# magloop_ad8129.net
KiCad netlist of a schematic drawn in EAGLE
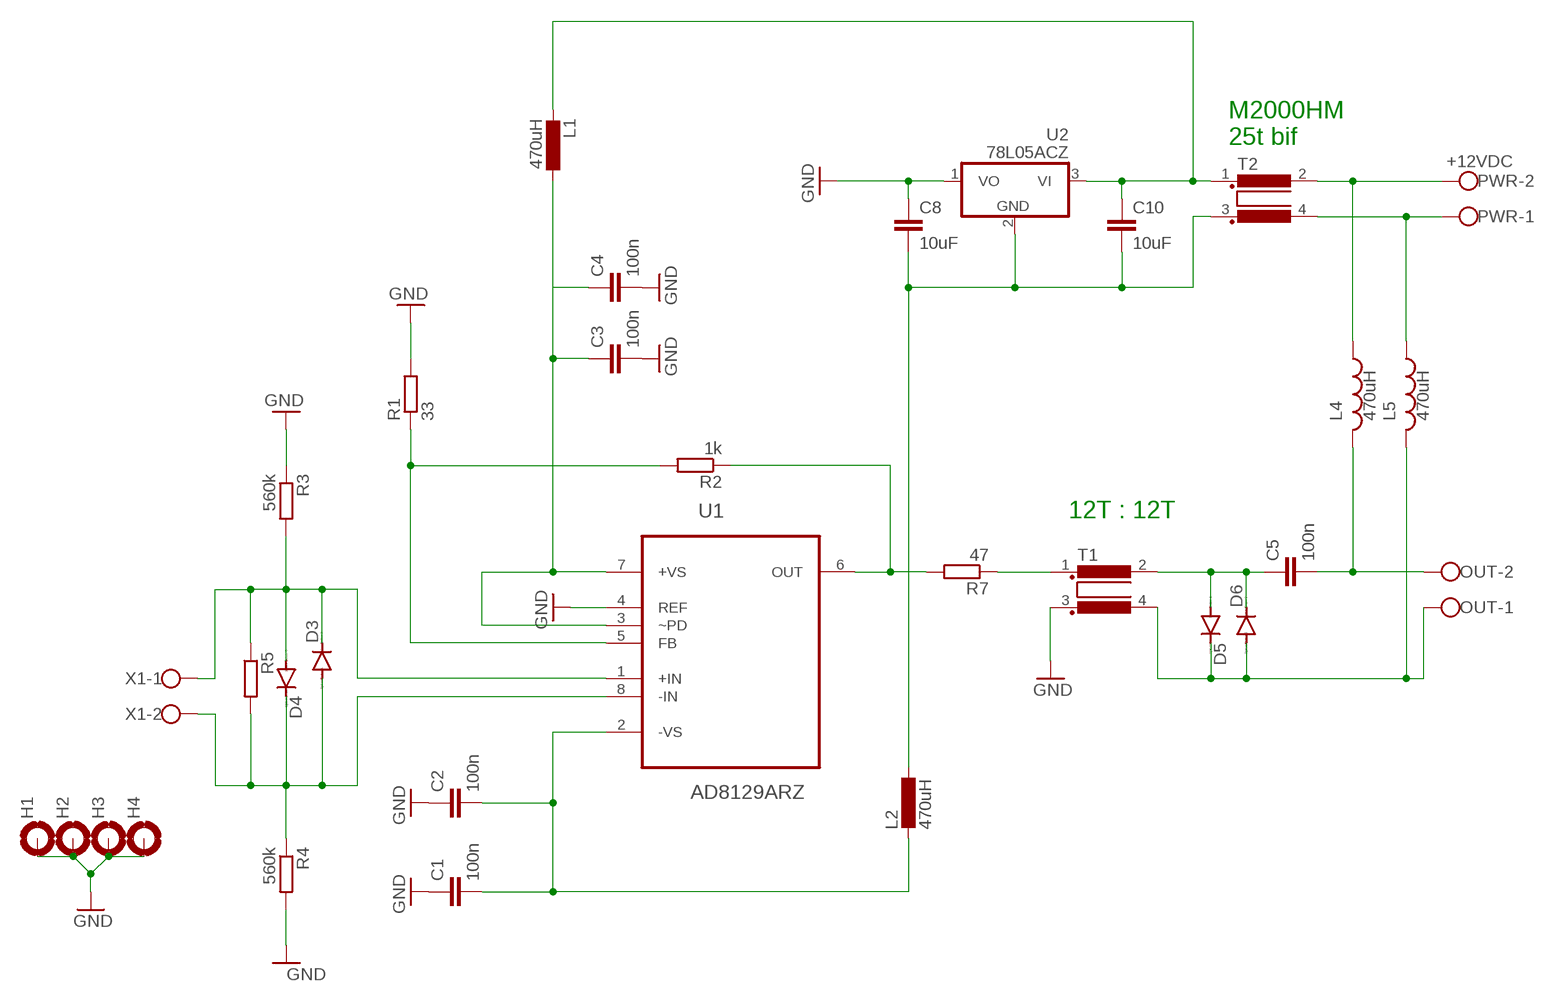
[diagram p0: schematic, sheet 1]

(export (version "E")
  (design (tool "Eeschema 10.0.6"))
  (components
    (comp (ref "C1")
      (value "100n")
      (footprint "eagle-import:C0805")
      (libsource (lib "eagle-import") (part "C_0805_SMD"))
    )
    (comp (ref "C2")
      (value "100n")
      (footprint "eagle-import:C0805")
      (libsource (lib "eagle-import") (part "C_0805_SMD"))
    )
    (comp (ref "C3")
      (value "100n")
      (footprint "eagle-import:C0805")
      (libsource (lib "eagle-import") (part "C_0805_SMD"))
    )
    (comp (ref "C4")
      (value "100n")
      (footprint "eagle-import:C0805")
      (libsource (lib "eagle-import") (part "C_0805_SMD"))
    )
    (comp (ref "C5")
      (value "100n")
      (footprint "eagle-import:C0805K")
      (libsource (lib "eagle-import") (part "C_0805_PTH"))
    )
    (comp (ref "C8")
      (value "10uF")
      (footprint "eagle-import:C1206K")
      (libsource (lib "eagle-import") (part "C-EUC1206K"))
    )
    (comp (ref "C10")
      (value "10uF")
      (footprint "eagle-import:C1206K")
      (libsource (lib "eagle-import") (part "C-EUC1206K"))
    )
    (comp (ref "D3")
      (value "LL4148")
      (footprint "eagle-import:SOD-123_MINI-SMA")
      (libsource (lib "eagle-import") (part "CGRM400-G1"))
    )
    (comp (ref "D4")
      (value "LL4148")
      (footprint "eagle-import:SOD-123_MINI-SMA")
      (libsource (lib "eagle-import") (part "CGRM400-G1"))
    )
    (comp (ref "D5")
      (value "CGRM4001-G")
      (footprint "eagle-import:SOD-123_MINI-SMA")
      (libsource (lib "eagle-import") (part "CGRM400-G1"))
    )
    (comp (ref "D6")
      (value "CGRM4001-G")
      (footprint "eagle-import:SOD-123_MINI-SMA")
      (libsource (lib "eagle-import") (part "CGRM400-G1"))
    )
    (comp (ref "H1")
      (value "MOUNT-PAD-ROUND3.0")
      (footprint "eagle-import:3,0-PAD")
      (libsource (lib "eagle-import") (part "MOUNT-PAD-ROUND3.0"))
    )
    (comp (ref "H2")
      (value "MOUNT-PAD-ROUND3.0")
      (footprint "eagle-import:3,0-PAD")
      (libsource (lib "eagle-import") (part "MOUNT-PAD-ROUND3.0"))
    )
    (comp (ref "H3")
      (value "MOUNT-PAD-ROUND3.0")
      (footprint "eagle-import:3,0-PAD")
      (libsource (lib "eagle-import") (part "MOUNT-PAD-ROUND3.0"))
    )
    (comp (ref "H4")
      (value "MOUNT-PAD-ROUND3.0")
      (footprint "eagle-import:3,0-PAD")
      (libsource (lib "eagle-import") (part "MOUNT-PAD-ROUND3.0"))
    )
    (comp (ref "L1")
      (value "470uH")
      (footprint "eagle-import:0207_10")
      (libsource (lib "eagle-import") (part "L-EU0207/10"))
    )
    (comp (ref "L2")
      (value "470uH")
      (footprint "eagle-import:0207_10")
      (libsource (lib "eagle-import") (part "L-EU0207/10"))
    )
    (comp (ref "L4")
      (value "470uH")
      (footprint "eagle-import:M0805")
      (libsource (lib "eagle-import") (part "L_0805_PTH"))
    )
    (comp (ref "L5")
      (value "470uH")
      (footprint "eagle-import:M0805")
      (libsource (lib "eagle-import") (part "L_0805_PTH"))
    )
    (comp (ref "OUT")
      (value "W237-102")
      (footprint "eagle-import:W237-102")
      (fields (field (name "MPN") "237-102"))
      (libsource (lib "eagle-import") (part "W237-102"))
    )
    (comp (ref "PWR")
      (value "+12VDC")
      (footprint "eagle-import:W237-102")
      (fields (field (name "MPN") "237-102"))
      (libsource (lib "eagle-import") (part "W237-102"))
    )
    (comp (ref "R1")
      (value "33")
      (footprint "eagle-import:R0805W")
      (libsource (lib "eagle-import") (part "R_0805_SMD"))
    )
    (comp (ref "R2")
      (value "1k")
      (footprint "eagle-import:R0805W")
      (libsource (lib "eagle-import") (part "R_0805_SMD"))
    )
    (comp (ref "R3")
      (value "560k")
      (footprint "eagle-import:R0805")
      (libsource (lib "eagle-import") (part "R_0805_PTH"))
    )
    (comp (ref "R4")
      (value "560k")
      (footprint "eagle-import:R0805")
      (libsource (lib "eagle-import") (part "R_0805_PTH"))
    )
    (comp (ref "R5")
      (value "R_0805_PTH")
      (footprint "eagle-import:R0805")
      (libsource (lib "eagle-import") (part "R_0805_PTH"))
    )
    (comp (ref "R7")
      (value "47")
      (footprint "eagle-import:R1206")
      (libsource (lib "eagle-import") (part "R-EU_R1206"))
    )
    (comp (ref "T1")
      (value "R1405UB1/2")
      (footprint "eagle-import:B1_2")
      (libsource (lib "eagle-import") (part "R1405UB1/2"))
    )
    (comp (ref "T2")
      (value "R1405UB1/2")
      (footprint "eagle-import:B1_2")
      (libsource (lib "eagle-import") (part "R1405UB1/2"))
    )
    (comp (ref "U1")
      (value "AD8129ARZ")
      (footprint "eagle-import:SOIC127P600X175-8N")
      (fields (field (name "MF") "Analog Devices"))
      (libsource (lib "eagle-import") (part "AD8129ARZ"))
    )
    (comp (ref "U2")
      (value "78L05ACZ")
      (footprint "eagle-import:TO-92")
      (fields (field (name "MF") "STMicroelectronics"))
      (libsource (lib "eagle-import") (part "78L05ACZ"))
    )
    (comp (ref "X1")
      (value "W237-102")
      (footprint "eagle-import:W237-102")
      (fields (field (name "MPN") "237-102"))
      (libsource (lib "eagle-import") (part "W237-102"))
    )
  )
  (nets
    (net (code "1") (name "GND") (class "Default")
      (node (ref "C1") (pin "1") (pinfunction "1_1") (pintype "passive"))
      (node (ref "C2") (pin "1") (pinfunction "1_1") (pintype "passive"))
      (node (ref "C3") (pin "2") (pinfunction "2_2") (pintype "passive"))
      (node (ref "C4") (pin "2") (pinfunction "2_2") (pintype "passive"))
      (node (ref "C8") (pin "1") (pinfunction "1_1") (pintype "passive"))
      (node (ref "H1") (pin "B3,0") (pinfunction "MOUNT_B3,0") (pintype "passive"))
      (node (ref "H2") (pin "B3,0") (pinfunction "MOUNT_B3,0") (pintype "passive"))
      (node (ref "H3") (pin "B3,0") (pinfunction "MOUNT_B3,0") (pintype "passive"))
      (node (ref "H4") (pin "B3,0") (pinfunction "MOUNT_B3,0") (pintype "passive"))
      (node (ref "R1") (pin "2") (pinfunction "2_2") (pintype "passive"))
      (node (ref "R3") (pin "1") (pinfunction "1_1") (pintype "passive"))
      (node (ref "R3") (pin "P$1") (pinfunction "1_P$1") (pintype "passive"))
      (node (ref "R4") (pin "2") (pinfunction "2_2") (pintype "passive"))
      (node (ref "R4") (pin "P$2") (pinfunction "2_P$2") (pintype "passive"))
      (node (ref "T1") (pin "3") (pinfunction "3_3") (pintype "passive"))
      (node (ref "U1") (pin "4") (pinfunction "REF_4") (pintype "input"))
      (node (ref "U2") (pin "1") (pinfunction "VO_1") (pintype "passive"))
    )
    (net (code "2") (name "Net-(C5-1-PadP$1)") (class "Default")
      (node (ref "C5") (pin "1") (pinfunction "1_1") (pintype "passive"))
      (node (ref "C5") (pin "P$1") (pinfunction "1_P$1") (pintype "passive"))
      (node (ref "D5") (pin "A") (pinfunction "A_A") (pintype "passive"))
      (node (ref "D6") (pin "C") (pinfunction "C_C") (pintype "passive"))
      (node (ref "T1") (pin "2") (pinfunction "2_2") (pintype "passive"))
    )
    (net (code "3") (name "Net-(OUTA-KL)") (class "Default")
      (node (ref "D5") (pin "C") (pinfunction "C_C") (pintype "passive"))
      (node (ref "D6") (pin "A") (pinfunction "A_A") (pintype "passive"))
      (node (ref "L5") (pin "2") (pinfunction "2_2") (pintype "passive"))
      (node (ref "L5") (pin "P$2") (pinfunction "2_P$2") (pintype "passive"))
      (node (ref "OUT") (pin "1") (pinfunction "KL_1") (pintype "passive"))
      (node (ref "T1") (pin "4") (pinfunction "4_4") (pintype "passive"))
    )
    (net (code "4") (name "Net-(OUTB-KL)") (class "Default")
      (node (ref "C5") (pin "2") (pinfunction "2_2") (pintype "passive"))
      (node (ref "C5") (pin "P$2") (pinfunction "2_P$2") (pintype "passive"))
      (node (ref "L4") (pin "2") (pinfunction "2_2") (pintype "passive"))
      (node (ref "L4") (pin "P$2") (pinfunction "2_P$2") (pintype "passive"))
      (node (ref "OUT") (pin "2") (pinfunction "KL_2") (pintype "passive"))
    )
    (net (code "5") (name "Net-(PWRA-KL)") (class "Default")
      (node (ref "L5") (pin "1") (pinfunction "1_1") (pintype "passive"))
      (node (ref "L5") (pin "P$1") (pinfunction "1_P$1") (pintype "passive"))
      (node (ref "PWR") (pin "1") (pinfunction "KL_1") (pintype "passive"))
      (node (ref "T2") (pin "4") (pinfunction "4_4") (pintype "passive"))
    )
    (net (code "6") (name "Net-(PWRB-KL)") (class "Default")
      (node (ref "L4") (pin "1") (pinfunction "1_1") (pintype "passive"))
      (node (ref "L4") (pin "P$1") (pinfunction "1_P$1") (pintype "passive"))
      (node (ref "PWR") (pin "2") (pinfunction "KL_2") (pintype "passive"))
      (node (ref "T2") (pin "2") (pinfunction "2_2") (pintype "passive"))
    )
    (net (code "7") (name "Net-(R7-Pad1)") (class "Default")
      (node (ref "R7") (pin "1") (pinfunction "1_1") (pintype "passive"))
      (node (ref "T1") (pin "1") (pinfunction "1_1") (pintype "passive"))
    )
    (net (code "8") (name "Net-(U1-+IN)") (class "Default")
      (node (ref "D3") (pin "C") (pinfunction "C_C") (pintype "passive"))
      (node (ref "D4") (pin "A") (pinfunction "A_A") (pintype "passive"))
      (node (ref "R3") (pin "2") (pinfunction "2_2") (pintype "passive"))
      (node (ref "R3") (pin "P$2") (pinfunction "2_P$2") (pintype "passive"))
      (node (ref "R5") (pin "1") (pinfunction "1_1") (pintype "passive"))
      (node (ref "R5") (pin "P$1") (pinfunction "1_P$1") (pintype "passive"))
      (node (ref "U1") (pin "1") (pinfunction "+IN_1") (pintype "input"))
      (node (ref "X1") (pin "1") (pinfunction "KL_1") (pintype "passive"))
    )
    (net (code "9") (name "Net-(U1-+VS)") (class "Default")
      (node (ref "C3") (pin "1") (pinfunction "1_1") (pintype "passive"))
      (node (ref "C4") (pin "1") (pinfunction "1_1") (pintype "passive"))
      (node (ref "L1") (pin "1") (pinfunction "1_1") (pintype "passive"))
      (node (ref "U1") (pin "3") (pinfunction "~{PD}_3") (pintype "passive"))
      (node (ref "U1") (pin "7") (pinfunction "+VS_7") (pintype "power_in"))
    )
    (net (code "10") (name "Net-(U1--IN)") (class "Default")
      (node (ref "D3") (pin "A") (pinfunction "A_A") (pintype "passive"))
      (node (ref "D4") (pin "C") (pinfunction "C_C") (pintype "passive"))
      (node (ref "R4") (pin "1") (pinfunction "1_1") (pintype "passive"))
      (node (ref "R4") (pin "P$1") (pinfunction "1_P$1") (pintype "passive"))
      (node (ref "R5") (pin "2") (pinfunction "2_2") (pintype "passive"))
      (node (ref "R5") (pin "P$2") (pinfunction "2_P$2") (pintype "passive"))
      (node (ref "U1") (pin "8") (pinfunction "-IN_8") (pintype "input"))
      (node (ref "X1") (pin "2") (pinfunction "KL_2") (pintype "passive"))
    )
    (net (code "11") (name "Net-(U1--VS)") (class "Default")
      (node (ref "C1") (pin "2") (pinfunction "2_2") (pintype "passive"))
      (node (ref "C2") (pin "2") (pinfunction "2_2") (pintype "passive"))
      (node (ref "L2") (pin "2") (pinfunction "2_2") (pintype "passive"))
      (node (ref "U1") (pin "2") (pinfunction "-VS_2") (pintype "power_in"))
    )
    (net (code "12") (name "Net-(U1-FB)") (class "Default")
      (node (ref "R1") (pin "1") (pinfunction "1_1") (pintype "passive"))
      (node (ref "R2") (pin "2") (pinfunction "2_2") (pintype "passive"))
      (node (ref "U1") (pin "5") (pinfunction "FB_5") (pintype "input"))
    )
    (net (code "13") (name "Net-(U1-OUT)") (class "Default")
      (node (ref "R2") (pin "1") (pinfunction "1_1") (pintype "passive"))
      (node (ref "R7") (pin "2") (pinfunction "2_2") (pintype "passive"))
      (node (ref "U1") (pin "6") (pinfunction "OUT_6") (pintype "output"))
    )
    (net (code "14") (name "Net-(U2-GND)") (class "Default")
      (node (ref "C10") (pin "2") (pinfunction "2_2") (pintype "passive"))
      (node (ref "C8") (pin "2") (pinfunction "2_2") (pintype "passive"))
      (node (ref "L2") (pin "1") (pinfunction "1_1") (pintype "passive"))
      (node (ref "T2") (pin "3") (pinfunction "3_3") (pintype "passive"))
      (node (ref "U2") (pin "2") (pinfunction "GND_2") (pintype "passive"))
    )
    (net (code "15") (name "Net-(U2-VI)") (class "Default")
      (node (ref "C10") (pin "1") (pinfunction "1_1") (pintype "passive"))
      (node (ref "L1") (pin "2") (pinfunction "2_2") (pintype "passive"))
      (node (ref "T2") (pin "1") (pinfunction "1_1") (pintype "passive"))
      (node (ref "U2") (pin "3") (pinfunction "VI_3") (pintype "input"))
    )
  )
)
